# DisplayBoard.net
KiCad netlist of a schematic drawn in Altium Designer
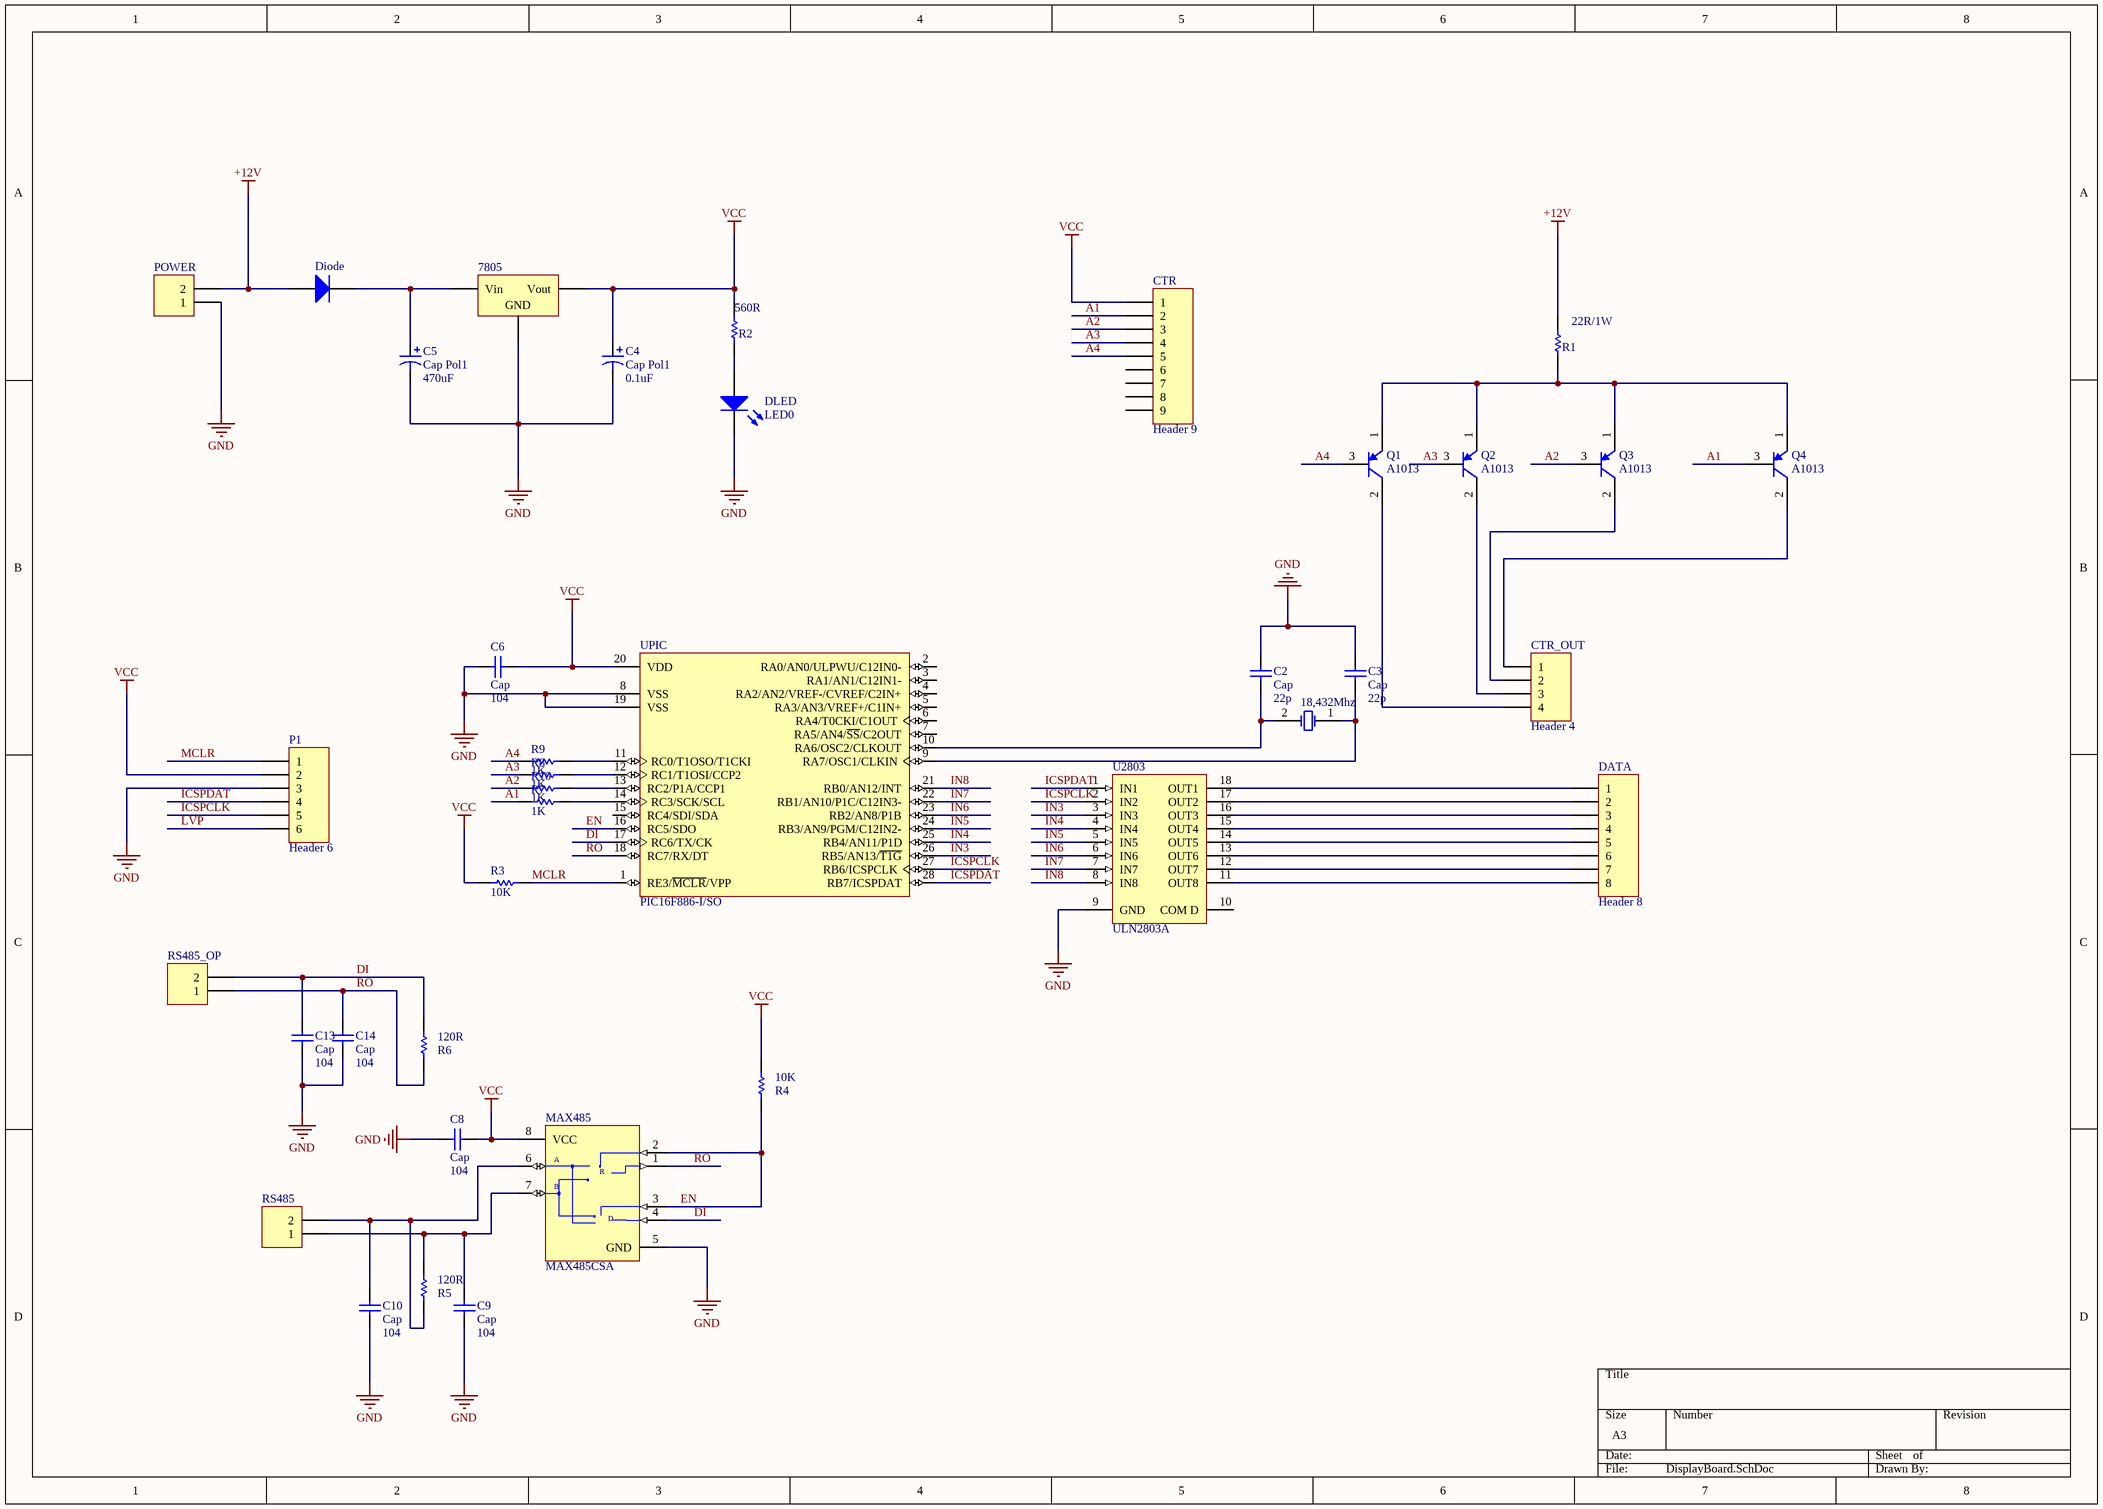
[diagram p0: DisplayBoard.SchDoc]

(export (version "E")
  (design (tool "Eeschema 10.0.6"))
  (components
    (comp (ref "18,432Mhz")
      (value "XTAL")
      (footprint "Device:Xtal12M")
      (description "Crystal Oscillator")
      (fields (field (name "PUBLISHER") "Altium Limited"))
      (libsource (lib "Miscellaneous Devices") (part "XTAL"))
    )
    (comp (ref "7805")
      (value "Volt Reg")
      (footprint "Device:78xx_NO")
      (description "Voltage Regulator")
      (fields (field (name "PUBLISHER") "Altium Limited"))
      (libsource (lib "Miscellaneous Devices") (part "Volt Reg"))
    )
    (comp (ref "C2")
      (value "Cap")
      (footprint "Device:tu_gom")
      (description "Capcitor")
      (fields (field (name "ALTIUM_VALUE") "22p"))
      (libsource (lib "Device_Component") (part "Ceramic"))
    )
    (comp (ref "C3")
      (value "Cap")
      (footprint "Device:tu_gom")
      (description "Capcitor")
      (fields (field (name "ALTIUM_VALUE") "22p"))
      (libsource (lib "Device_Component") (part "Ceramic"))
    )
    (comp (ref "C4")
      (value "Cap Pol1")
      (footprint "Device:tu 100uF/50v")
      (description "Polarized Capacitor (Radial)")
      (fields (field (name "ALTIUM_VALUE") "0.1uF") (field (name "PUBLISHER") "Altium Limited"))
      (libsource (lib "Miscellaneous Devices") (part "Cap Pol1"))
    )
    (comp (ref "C5")
      (value "Cap Pol1")
      (footprint "Device:TU 470uF/50V")
      (description "Polarized Capacitor (Radial)")
      (fields (field (name "ALTIUM_VALUE") "470uF") (field (name "PUBLISHER") "Altium Limited"))
      (libsource (lib "Miscellaneous Devices") (part "Cap Pol1"))
    )
    (comp (ref "C6")
      (value "Cap")
      (footprint "Device:tu_gom")
      (description "Capcitor")
      (fields (field (name "ALTIUM_VALUE") "104"))
      (libsource (lib "Device_Component") (part "Ceramic"))
    )
    (comp (ref "C8")
      (value "Cap")
      (footprint "Device:tu_gom")
      (description "Capcitor")
      (fields (field (name "ALTIUM_VALUE") "104"))
      (libsource (lib "Device_Component") (part "Ceramic"))
    )
    (comp (ref "C9")
      (value "Cap")
      (footprint "Device:tu_gom")
      (description "Capcitor")
      (fields (field (name "ALTIUM_VALUE") "104"))
      (libsource (lib "Device_Component") (part "Ceramic"))
    )
    (comp (ref "C10")
      (value "Cap")
      (footprint "Device:tu_gom")
      (description "Capcitor")
      (fields (field (name "ALTIUM_VALUE") "104"))
      (libsource (lib "Device_Component") (part "Ceramic"))
    )
    (comp (ref "C13")
      (value "Cap")
      (footprint "Device:tu_gom")
      (description "Capcitor")
      (fields (field (name "ALTIUM_VALUE") "104"))
      (libsource (lib "Device_Component") (part "Ceramic"))
    )
    (comp (ref "C14")
      (value "Cap")
      (footprint "Device:tu_gom")
      (description "Capcitor")
      (fields (field (name "ALTIUM_VALUE") "104"))
      (libsource (lib "Device_Component") (part "Ceramic"))
    )
    (comp (ref "CTR")
      (value "Header 9")
      (footprint "HDR1X9")
      (description "Header, 9-Pin")
      (fields (field (name "PUBLISHER") "Altium Limited"))
      (libsource (lib "Miscellaneous Connectors") (part "Header 9"))
    )
    (comp (ref "CTR_OUT")
      (value "Header 4")
      (footprint "Device:CAP 4")
      (description "Header, 4-Pin")
      (fields (field (name "PUBLISHER") "Altium Limited"))
      (libsource (lib "Miscellaneous Connectors") (part "Header 4"))
    )
    (comp (ref "DATA")
      (value "Header 8")
      (footprint "Device:Cap_8")
      (description "Header, 8-Pin")
      (fields (field (name "PUBLISHER") "Altium Limited"))
      (libsource (lib "Miscellaneous Connectors") (part "Header 8"))
    )
    (comp (ref "Diode")
      (value "Diode")
      (footprint "Device:D_2A")
      (description "Default Diode")
      (fields (field (name "PUBLISHER") "Altium Limited"))
      (libsource (lib "Miscellaneous Devices") (part "Diode"))
    )
    (comp (ref "DLED")
      (value "LED0")
      (footprint "Device:LED_3")
      (description "Typical INFRARED GaAs LED")
      (fields (field (name "PUBLISHER") "Altium Limited"))
      (libsource (lib "Miscellaneous Devices") (part "LED0"))
    )
    (comp (ref "MAX485")
      (value "MAX485CSA")
      (footprint "NSO8_N")
      (description "Low-Power, Slew-Rate-Limited RS-485/RS-422 Transceiver")
      (fields (field (name "PUBLISHER") "Altium Limited"))
      (libsource (lib "Maxim Communication Transceiver") (part "MAX485CSA"))
    )
    (comp (ref "P1")
      (value "Header 6")
      (footprint "HDR1X6")
      (description "Header, 6-Pin")
      (fields (field (name "PUBLISHER") "Altium Limited"))
      (libsource (lib "Miscellaneous Connectors") (part "Header 6"))
    )
    (comp (ref "POWER")
      (value "Header 2")
      (footprint "Device:Header2 - duplicate")
      (description "Header, 2-Pin")
      (fields (field (name "PUBLISHER") "Altium Limited"))
      (libsource (lib "Miscellaneous Connectors") (part "Header 2"))
    )
    (comp (ref "Q1")
      (value "A1013")
      (footprint "Device:A1013")
      (description "PNP Bipolar Transistor")
      (fields (field (name "PUBLISHER") "Altium Limited"))
      (libsource (lib "Miscellaneous Devices") (part "PNP"))
    )
    (comp (ref "Q2")
      (value "A1013")
      (footprint "Device:A1013")
      (description "PNP Bipolar Transistor")
      (fields (field (name "PUBLISHER") "Altium Limited"))
      (libsource (lib "Miscellaneous Devices") (part "PNP"))
    )
    (comp (ref "Q3")
      (value "A1013")
      (footprint "Device:A1013")
      (description "PNP Bipolar Transistor")
      (fields (field (name "PUBLISHER") "Altium Limited"))
      (libsource (lib "Miscellaneous Devices") (part "PNP"))
    )
    (comp (ref "Q4")
      (value "A1013")
      (footprint "Device:A1013")
      (description "PNP Bipolar Transistor")
      (fields (field (name "PUBLISHER") "Altium Limited"))
      (libsource (lib "Miscellaneous Devices") (part "PNP"))
    )
    (comp (ref "R1")
      (value "22R/1W")
      (footprint "Device:R_CS220/470/1W")
      (libsource (lib "Device_Component") (part "Res"))
    )
    (comp (ref "R2")
      (value "560R")
      (footprint "Device:R_Nor")
      (libsource (lib "Device_Component") (part "Res"))
    )
    (comp (ref "R3")
      (value "10K")
      (footprint "Device:R_Nor")
      (libsource (lib "Device_Component") (part "Res"))
    )
    (comp (ref "R4")
      (value "10K")
      (footprint "Device:R_Nor")
      (libsource (lib "Device_Component") (part "Res"))
    )
    (comp (ref "R5")
      (value "120R")
      (footprint "Device:R_Nor")
      (libsource (lib "Device_Component") (part "Res"))
    )
    (comp (ref "R6")
      (value "120R")
      (footprint "Device:R_Nor")
      (libsource (lib "Device_Component") (part "Res"))
    )
    (comp (ref "R7")
      (value "1K")
      (footprint "Device:R_Nor")
      (libsource (lib "Device_Component") (part "Res"))
    )
    (comp (ref "R8")
      (value "1K")
      (footprint "Device:R_Nor")
      (libsource (lib "Device_Component") (part "Res"))
    )
    (comp (ref "R9")
      (value "1K")
      (footprint "Device:R_Nor")
      (libsource (lib "Device_Component") (part "Res"))
    )
    (comp (ref "R10")
      (value "1K")
      (footprint "Device:R_Nor")
      (libsource (lib "Device_Component") (part "Res"))
    )
    (comp (ref "RS485")
      (value "Header 2")
      (footprint "Device:Header2 - duplicate")
      (description "Header, 2-Pin")
      (fields (field (name "PUBLISHER") "Altium Limited"))
      (libsource (lib "Miscellaneous Connectors") (part "Header 2"))
    )
    (comp (ref "RS485_OP")
      (value "Header 2")
      (footprint "Device:Header2 - duplicate")
      (description "Header, 2-Pin")
      (fields (field (name "PUBLISHER") "Altium Limited"))
      (libsource (lib "Miscellaneous Connectors") (part "Header 2"))
    )
    (comp (ref "U2803")
      (value "ULN2803A")
      (footprint "DIP18")
      (description "Eight Darlington Array")
      (fields (field (name "PUBLISHER") "Altium Limited"))
      (libsource (lib "ST Interface Darlington Driver") (part "ULN2803A"))
    )
    (comp (ref "UPIC")
      (value "PIC16F886-I/SO")
      (footprint "SOIC-SO28_L")
      (fields (field (name "PUBLISHER") "Altium Limited"))
      (libsource (lib "Microchip Microcontroller 8-Bit PIC16") (part "PIC16F886-I/SO"))
    )
  )
  (nets
    (net (code "1") (name "+12V") (class "Default")
      (node (ref "Diode") (pin "1") (pinfunction "A_1") (pintype "passive"))
      (node (ref "POWER") (pin "2") (pinfunction "2_2") (pintype "passive"))
      (node (ref "R1") (pin "2") (pinfunction "2_2") (pintype "passive"))
    )
    (net (code "2") (name "/A1") (class "Default")
      (node (ref "CTR") (pin "2") (pinfunction "2_2") (pintype "passive"))
      (node (ref "Q4") (pin "3") (pinfunction "B_3") (pintype "passive"))
      (node (ref "R7") (pin "2") (pinfunction "2_2") (pintype "passive"))
    )
    (net (code "3") (name "/A2") (class "Default")
      (node (ref "CTR") (pin "3") (pinfunction "3_3") (pintype "passive"))
      (node (ref "Q3") (pin "3") (pinfunction "B_3") (pintype "passive"))
      (node (ref "R10") (pin "2") (pinfunction "2_2") (pintype "passive"))
    )
    (net (code "4") (name "/A3") (class "Default")
      (node (ref "CTR") (pin "4") (pinfunction "4_4") (pintype "passive"))
      (node (ref "Q2") (pin "3") (pinfunction "B_3") (pintype "passive"))
      (node (ref "R8") (pin "2") (pinfunction "2_2") (pintype "passive"))
    )
    (net (code "5") (name "/A4") (class "Default")
      (node (ref "CTR") (pin "5") (pinfunction "5_5") (pintype "passive"))
      (node (ref "Q1") (pin "3") (pinfunction "B_3") (pintype "passive"))
      (node (ref "R9") (pin "2") (pinfunction "2_2") (pintype "passive"))
    )
    (net (code "6") (name "/DI") (class "Default")
      (node (ref "C13") (pin "2") (pinfunction "2_2") (pintype "passive"))
      (node (ref "MAX485") (pin "4") (pinfunction "DI_4") (pintype "input"))
      (node (ref "R6") (pin "2") (pinfunction "2_2") (pintype "passive"))
      (node (ref "RS485_OP") (pin "2") (pinfunction "2_2") (pintype "passive"))
      (node (ref "UPIC") (pin "17") (pinfunction "RC6/TX/CK_17") (pintype "bidirectional"))
    )
    (net (code "7") (name "/EN") (class "Default")
      (node (ref "MAX485") (pin "2") (pinfunction "~{RE}_2") (pintype "input"))
      (node (ref "MAX485") (pin "3") (pinfunction "DE_3") (pintype "input"))
      (node (ref "R4") (pin "1") (pinfunction "1_1") (pintype "passive"))
      (node (ref "UPIC") (pin "16") (pinfunction "RC5/SDO_16") (pintype "bidirectional"))
    )
    (net (code "8") (name "/ICSPCLK") (class "Default")
      (node (ref "P1") (pin "5") (pinfunction "5_5") (pintype "passive"))
      (node (ref "U2803") (pin "2") (pinfunction "IN2_2") (pintype "input"))
      (node (ref "UPIC") (pin "27") (pinfunction "RB6/ICSPCLK_27") (pintype "bidirectional"))
    )
    (net (code "9") (name "/ICSPDAT") (class "Default")
      (node (ref "P1") (pin "4") (pinfunction "4_4") (pintype "passive"))
      (node (ref "U2803") (pin "1") (pinfunction "IN1_1") (pintype "input"))
      (node (ref "UPIC") (pin "28") (pinfunction "RB7/ICSPDAT_28") (pintype "bidirectional"))
    )
    (net (code "10") (name "/IN3") (class "Default")
      (node (ref "U2803") (pin "3") (pinfunction "IN3_3") (pintype "input"))
      (node (ref "UPIC") (pin "26") (pinfunction "RB5/AN13/~{T1G}_26") (pintype "bidirectional"))
    )
    (net (code "11") (name "/IN4") (class "Default")
      (node (ref "U2803") (pin "4") (pinfunction "IN4_4") (pintype "input"))
      (node (ref "UPIC") (pin "25") (pinfunction "RB4/AN11/P1D_25") (pintype "bidirectional"))
    )
    (net (code "12") (name "/IN5") (class "Default")
      (node (ref "U2803") (pin "5") (pinfunction "IN5_5") (pintype "input"))
      (node (ref "UPIC") (pin "24") (pinfunction "RB3/AN9/PGM/C12IN2-_24") (pintype "bidirectional"))
    )
    (net (code "13") (name "/IN6") (class "Default")
      (node (ref "U2803") (pin "6") (pinfunction "IN6_6") (pintype "input"))
      (node (ref "UPIC") (pin "23") (pinfunction "RB2/AN8/P1B_23") (pintype "bidirectional"))
    )
    (net (code "14") (name "/IN7") (class "Default")
      (node (ref "U2803") (pin "7") (pinfunction "IN7_7") (pintype "input"))
      (node (ref "UPIC") (pin "22") (pinfunction "RB1/AN10/P1C/C12IN3-_22") (pintype "bidirectional"))
    )
    (net (code "15") (name "/IN8") (class "Default")
      (node (ref "U2803") (pin "8") (pinfunction "IN8_8") (pintype "input"))
      (node (ref "UPIC") (pin "21") (pinfunction "RB0/AN12/INT_21") (pintype "bidirectional"))
    )
    (net (code "16") (name "/LVP") (class "Default")
      (node (ref "P1") (pin "6") (pinfunction "6_6") (pintype "passive"))
    )
    (net (code "17") (name "/MCLR") (class "Default")
      (node (ref "P1") (pin "1") (pinfunction "1_1") (pintype "passive"))
      (node (ref "R3") (pin "1") (pinfunction "1_1") (pintype "passive"))
      (node (ref "UPIC") (pin "1") (pinfunction "RE3/~{MCLR}/VPP_1") (pintype "bidirectional"))
    )
    (net (code "18") (name "/RO") (class "Default")
      (node (ref "C14") (pin "2") (pinfunction "2_2") (pintype "passive"))
      (node (ref "MAX485") (pin "1") (pinfunction "RO_1") (pintype "output"))
      (node (ref "R6") (pin "1") (pinfunction "1_1") (pintype "passive"))
      (node (ref "RS485_OP") (pin "1") (pinfunction "1_1") (pintype "passive"))
      (node (ref "UPIC") (pin "18") (pinfunction "RC7/RX/DT_18") (pintype "bidirectional"))
    )
    (net (code "19") (name "GND") (class "Default")
      (node (ref "7805") (pin "2") (pinfunction "GND_2") (pintype "passive"))
      (node (ref "C10") (pin "1") (pinfunction "1_1") (pintype "passive"))
      (node (ref "C13") (pin "1") (pinfunction "1_1") (pintype "passive"))
      (node (ref "C14") (pin "1") (pinfunction "1_1") (pintype "passive"))
      (node (ref "C2") (pin "2") (pinfunction "2_2") (pintype "passive"))
      (node (ref "C3") (pin "2") (pinfunction "2_2") (pintype "passive"))
      (node (ref "C4") (pin "2") (pinfunction "2_2") (pintype "passive"))
      (node (ref "C5") (pin "2") (pinfunction "2_2") (pintype "passive"))
      (node (ref "C6") (pin "2") (pinfunction "2_2") (pintype "passive"))
      (node (ref "C8") (pin "1") (pinfunction "1_1") (pintype "passive"))
      (node (ref "C9") (pin "1") (pinfunction "1_1") (pintype "passive"))
      (node (ref "DLED") (pin "2") (pinfunction "K_2") (pintype "passive"))
      (node (ref "MAX485") (pin "5") (pinfunction "GND_5") (pintype "power_in"))
      (node (ref "P1") (pin "3") (pinfunction "3_3") (pintype "passive"))
      (node (ref "POWER") (pin "1") (pinfunction "1_1") (pintype "passive"))
      (node (ref "U2803") (pin "9") (pinfunction "GND_9") (pintype "power_in"))
      (node (ref "UPIC") (pin "19") (pinfunction "VSS_19") (pintype "power_in"))
      (node (ref "UPIC") (pin "8") (pinfunction "VSS_8") (pintype "power_in"))
    )
    (net (code "20") (name "Net-(18,432Mhz-OSC1)") (class "Default")
      (node (ref "18,432Mhz") (pin "1") (pinfunction "OSC1_1") (pintype "passive"))
      (node (ref "C3") (pin "1") (pinfunction "1_1") (pintype "passive"))
      (node (ref "UPIC") (pin "9") (pinfunction "RA7/OSC1/CLKIN_9") (pintype "bidirectional"))
    )
    (net (code "21") (name "Net-(18,432Mhz-OSC2)") (class "Default")
      (node (ref "18,432Mhz") (pin "2") (pinfunction "OSC2_2") (pintype "passive"))
      (node (ref "C2") (pin "1") (pinfunction "1_1") (pintype "passive"))
      (node (ref "UPIC") (pin "10") (pinfunction "RA6/OSC2/CLKOUT_10") (pintype "bidirectional"))
    )
    (net (code "22") (name "Net-(7805-Vin)") (class "Default")
      (node (ref "7805") (pin "1") (pinfunction "Vin_1") (pintype "passive"))
      (node (ref "C5") (pin "1") (pinfunction "1_1") (pintype "passive"))
      (node (ref "Diode") (pin "2") (pinfunction "K_2") (pintype "passive"))
    )
    (net (code "23") (name "Net-(DLED-A)") (class "Default")
      (node (ref "DLED") (pin "1") (pinfunction "A_1") (pintype "passive"))
      (node (ref "R2") (pin "1") (pinfunction "1_1") (pintype "passive"))
    )
    (net (code "24") (name "Net-(MAX485-A)") (class "Default")
      (node (ref "C10") (pin "2") (pinfunction "2_2") (pintype "passive"))
      (node (ref "MAX485") (pin "6") (pinfunction "A_6") (pintype "bidirectional"))
      (node (ref "R5") (pin "1") (pinfunction "1_1") (pintype "passive"))
      (node (ref "RS485") (pin "2") (pinfunction "2_2") (pintype "passive"))
    )
    (net (code "25") (name "Net-(MAX485-B)") (class "Default")
      (node (ref "C9") (pin "2") (pinfunction "2_2") (pintype "passive"))
      (node (ref "MAX485") (pin "7") (pinfunction "B_7") (pintype "bidirectional"))
      (node (ref "R5") (pin "2") (pinfunction "2_2") (pintype "passive"))
      (node (ref "RS485") (pin "1") (pinfunction "1_1") (pintype "passive"))
    )
    (net (code "26") (name "Net-(Q1-C)") (class "Default")
      (node (ref "CTR_OUT") (pin "4") (pinfunction "4_4") (pintype "passive"))
      (node (ref "Q1") (pin "2") (pinfunction "C_2") (pintype "passive"))
    )
    (net (code "27") (name "Net-(Q1-E)") (class "Default")
      (node (ref "Q1") (pin "1") (pinfunction "E_1") (pintype "passive"))
      (node (ref "Q2") (pin "1") (pinfunction "E_1") (pintype "passive"))
      (node (ref "Q3") (pin "1") (pinfunction "E_1") (pintype "passive"))
      (node (ref "Q4") (pin "1") (pinfunction "E_1") (pintype "passive"))
      (node (ref "R1") (pin "1") (pinfunction "1_1") (pintype "passive"))
    )
    (net (code "28") (name "Net-(Q2-C)") (class "Default")
      (node (ref "CTR_OUT") (pin "3") (pinfunction "3_3") (pintype "passive"))
      (node (ref "Q2") (pin "2") (pinfunction "C_2") (pintype "passive"))
    )
    (net (code "29") (name "Net-(Q3-C)") (class "Default")
      (node (ref "CTR_OUT") (pin "2") (pinfunction "2_2") (pintype "passive"))
      (node (ref "Q3") (pin "2") (pinfunction "C_2") (pintype "passive"))
    )
    (net (code "30") (name "Net-(Q4-C)") (class "Default")
      (node (ref "CTR_OUT") (pin "1") (pinfunction "1_1") (pintype "passive"))
      (node (ref "Q4") (pin "2") (pinfunction "C_2") (pintype "passive"))
    )
    (net (code "31") (name "Net-(U2803-OUT1)") (class "Default")
      (node (ref "DATA") (pin "1") (pinfunction "1_1") (pintype "passive"))
      (node (ref "U2803") (pin "18") (pinfunction "OUT1_18") (pintype "open_collector"))
    )
    (net (code "32") (name "Net-(U2803-OUT2)") (class "Default")
      (node (ref "DATA") (pin "2") (pinfunction "2_2") (pintype "passive"))
      (node (ref "U2803") (pin "17") (pinfunction "OUT2_17") (pintype "open_collector"))
    )
    (net (code "33") (name "Net-(U2803-OUT3)") (class "Default")
      (node (ref "DATA") (pin "3") (pinfunction "3_3") (pintype "passive"))
      (node (ref "U2803") (pin "16") (pinfunction "OUT3_16") (pintype "open_collector"))
    )
    (net (code "34") (name "Net-(U2803-OUT4)") (class "Default")
      (node (ref "DATA") (pin "4") (pinfunction "4_4") (pintype "passive"))
      (node (ref "U2803") (pin "15") (pinfunction "OUT4_15") (pintype "open_collector"))
    )
    (net (code "35") (name "Net-(U2803-OUT5)") (class "Default")
      (node (ref "DATA") (pin "5") (pinfunction "5_5") (pintype "passive"))
      (node (ref "U2803") (pin "14") (pinfunction "OUT5_14") (pintype "open_collector"))
    )
    (net (code "36") (name "Net-(U2803-OUT6)") (class "Default")
      (node (ref "DATA") (pin "6") (pinfunction "6_6") (pintype "passive"))
      (node (ref "U2803") (pin "13") (pinfunction "OUT6_13") (pintype "open_collector"))
    )
    (net (code "37") (name "Net-(U2803-OUT7)") (class "Default")
      (node (ref "DATA") (pin "7") (pinfunction "7_7") (pintype "passive"))
      (node (ref "U2803") (pin "12") (pinfunction "OUT7_12") (pintype "open_collector"))
    )
    (net (code "38") (name "Net-(U2803-OUT8)") (class "Default")
      (node (ref "DATA") (pin "8") (pinfunction "8_8") (pintype "passive"))
      (node (ref "U2803") (pin "11") (pinfunction "OUT8_11") (pintype "open_collector"))
    )
    (net (code "39") (name "Net-(UPIC-RC0{slash}T1OSO{slash}T1CKI)") (class "Default")
      (node (ref "R9") (pin "1") (pinfunction "1_1") (pintype "passive"))
      (node (ref "UPIC") (pin "11") (pinfunction "RC0/T1OSO/T1CKI_11") (pintype "bidirectional"))
    )
    (net (code "40") (name "Net-(UPIC-RC1{slash}T1OSI{slash}CCP2)") (class "Default")
      (node (ref "R8") (pin "1") (pinfunction "1_1") (pintype "passive"))
      (node (ref "UPIC") (pin "12") (pinfunction "RC1/T1OSI/CCP2_12") (pintype "bidirectional"))
    )
    (net (code "41") (name "Net-(UPIC-RC2{slash}P1A{slash}CCP1)") (class "Default")
      (node (ref "R10") (pin "1") (pinfunction "1_1") (pintype "passive"))
      (node (ref "UPIC") (pin "13") (pinfunction "RC2/P1A/CCP1_13") (pintype "bidirectional"))
    )
    (net (code "42") (name "Net-(UPIC-RC3{slash}SCK{slash}SCL)") (class "Default")
      (node (ref "R7") (pin "1") (pinfunction "1_1") (pintype "passive"))
      (node (ref "UPIC") (pin "14") (pinfunction "RC3/SCK/SCL_14") (pintype "bidirectional"))
    )
    (net (code "43") (name "VCC") (class "Default")
      (node (ref "7805") (pin "3") (pinfunction "Vout_3") (pintype "passive"))
      (node (ref "C4") (pin "1") (pinfunction "1_1") (pintype "passive"))
      (node (ref "C6") (pin "1") (pinfunction "1_1") (pintype "passive"))
      (node (ref "C8") (pin "2") (pinfunction "2_2") (pintype "passive"))
      (node (ref "CTR") (pin "1") (pinfunction "1_1") (pintype "passive"))
      (node (ref "MAX485") (pin "8") (pinfunction "VCC_8") (pintype "power_in"))
      (node (ref "P1") (pin "2") (pinfunction "2_2") (pintype "passive"))
      (node (ref "R2") (pin "2") (pinfunction "2_2") (pintype "passive"))
      (node (ref "R3") (pin "2") (pinfunction "2_2") (pintype "passive"))
      (node (ref "R4") (pin "2") (pinfunction "2_2") (pintype "passive"))
      (node (ref "UPIC") (pin "20") (pinfunction "VDD_20") (pintype "power_in"))
    )
    (net (code "44") (name "unconnected-(CTR-Pad6)") (class "Default")
      (node (ref "CTR") (pin "6") (pinfunction "6_6") (pintype "passive"))
    )
    (net (code "45") (name "unconnected-(CTR-Pad7)") (class "Default")
      (node (ref "CTR") (pin "7") (pinfunction "7_7") (pintype "passive"))
    )
    (net (code "46") (name "unconnected-(CTR-Pad8)") (class "Default")
      (node (ref "CTR") (pin "8") (pinfunction "8_8") (pintype "passive"))
    )
    (net (code "47") (name "unconnected-(CTR-Pad9)") (class "Default")
      (node (ref "CTR") (pin "9") (pinfunction "9_9") (pintype "passive"))
    )
    (net (code "48") (name "unconnected-(U2803-COM_D-Pad10)") (class "Default")
      (node (ref "U2803") (pin "10") (pinfunction "COM_D_10") (pintype "passive"))
    )
    (net (code "49") (name "unconnected-(UPIC-RA0{slash}AN0{slash}ULPWU{slash}C12IN0--Pad2)") (class "Default")
      (node (ref "UPIC") (pin "2") (pinfunction "RA0/AN0/ULPWU/C12IN0-_2") (pintype "bidirectional"))
    )
    (net (code "50") (name "unconnected-(UPIC-RA1{slash}AN1{slash}C12IN1--Pad3)") (class "Default")
      (node (ref "UPIC") (pin "3") (pinfunction "RA1/AN1/C12IN1-_3") (pintype "bidirectional"))
    )
    (net (code "51") (name "unconnected-(UPIC-RA2{slash}AN2{slash}VREF-{slash}CVREF{slash}C2IN+-Pad4)") (class "Default")
      (node (ref "UPIC") (pin "4") (pinfunction "RA2/AN2/VREF-/CVREF/C2IN+_4") (pintype "bidirectional"))
    )
    (net (code "52") (name "unconnected-(UPIC-RA3{slash}AN3{slash}VREF+{slash}C1IN+-Pad5)") (class "Default")
      (node (ref "UPIC") (pin "5") (pinfunction "RA3/AN3/VREF+/C1IN+_5") (pintype "bidirectional"))
    )
    (net (code "53") (name "unconnected-(UPIC-RA4{slash}T0CKI{slash}C1OUT-Pad6)") (class "Default")
      (node (ref "UPIC") (pin "6") (pinfunction "RA4/T0CKI/C1OUT_6") (pintype "bidirectional"))
    )
    (net (code "54") (name "unconnected-(UPIC-RA5{slash}AN4{slash}~{SS}{slash}C2OUT-Pad7)") (class "Default")
      (node (ref "UPIC") (pin "7") (pinfunction "RA5/AN4/~{SS}/C2OUT_7") (pintype "bidirectional"))
    )
    (net (code "55") (name "unconnected-(UPIC-RC4{slash}SDI{slash}SDA-Pad15)") (class "Default")
      (node (ref "UPIC") (pin "15") (pinfunction "RC4/SDI/SDA_15") (pintype "bidirectional"))
    )
  )
)
